# GWLSensorv5.net
KiCad netlist of a schematic drawn in EAGLE
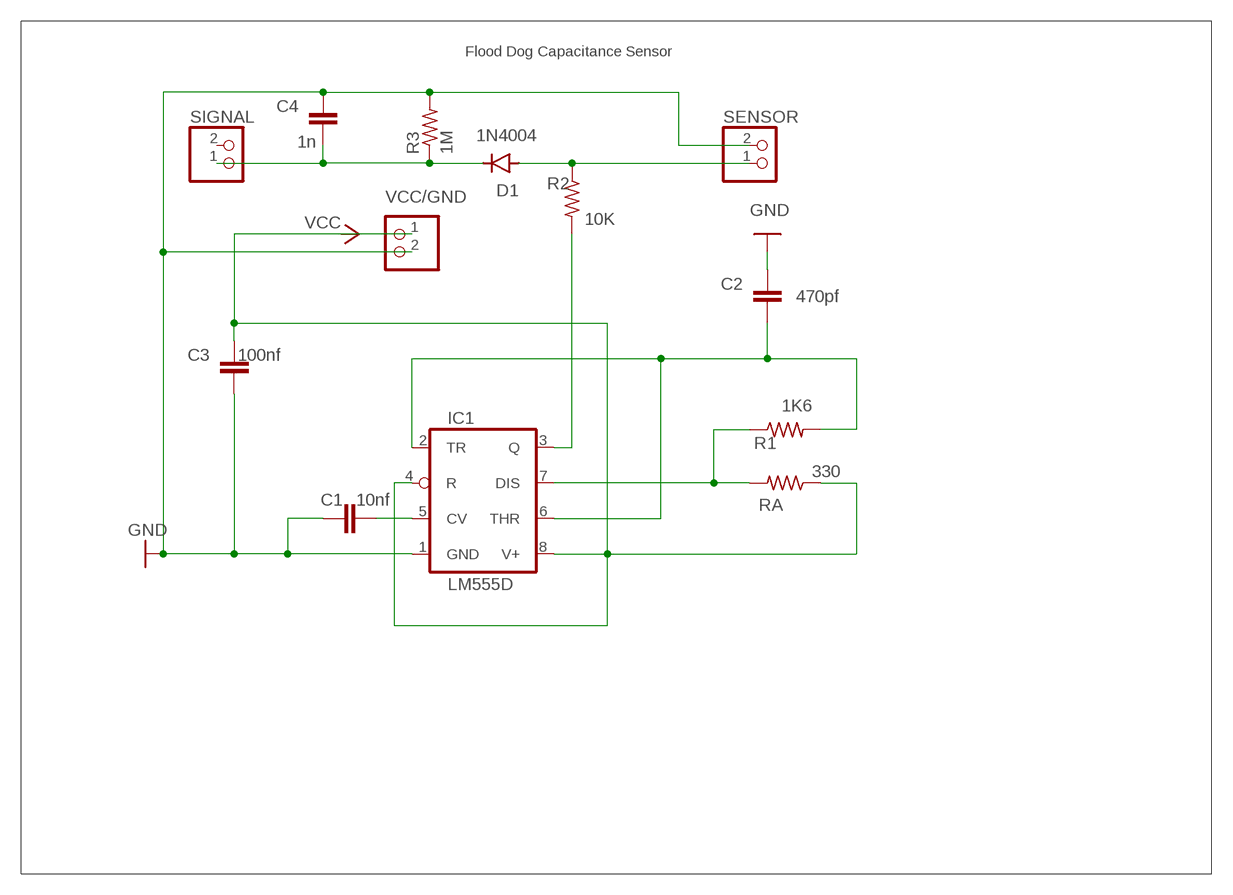
[diagram p0: schematic, sheet 1]

(export (version "E")
  (design (tool "Eeschema 10.0.6"))
  (components
    (comp (ref "C1")
      (value "10nf")
      (footprint "eagle-import:C0805")
      (libsource (lib "eagle-import") (part "C-EUC0805"))
    )
    (comp (ref "C2")
      (value "470pf")
      (footprint "eagle-import:C0805")
      (libsource (lib "eagle-import") (part "C-EUC0805"))
    )
    (comp (ref "C3")
      (value "100nf")
      (footprint "eagle-import:C0805")
      (libsource (lib "eagle-import") (part "C-EUC0805"))
    )
    (comp (ref "C4")
      (value "1n")
      (footprint "eagle-import:C0805")
      (libsource (lib "eagle-import") (part "C-EUC0805"))
    )
    (comp (ref "D1")
      (value "1N4004")
      (footprint "eagle-import:DO41-10")
      (libsource (lib "eagle-import") (part "1N4004"))
    )
    (comp (ref "IC1")
      (value "LM555D")
      (footprint "eagle-import:SO08")
      (libsource (lib "eagle-import") (part "555DLM"))
    )
    (comp (ref "R1")
      (value "1K6")
      (footprint "eagle-import:R0805")
      (libsource (lib "eagle-import") (part "R-US_R0805"))
    )
    (comp (ref "R2")
      (value "10K")
      (footprint "eagle-import:R0805")
      (libsource (lib "eagle-import") (part "R-US_R0805"))
    )
    (comp (ref "R3")
      (value "1M")
      (footprint "eagle-import:R0805")
      (libsource (lib "eagle-import") (part "R-US_R0805"))
    )
    (comp (ref "RA")
      (value "330")
      (footprint "eagle-import:R0805")
      (libsource (lib "eagle-import") (part "R-US_R0805"))
    )
    (comp (ref "SENSOR")
      (value "JST_2PIN-SMT")
      (footprint "eagle-import:JST-PH-2-SMT")
      (libsource (lib "eagle-import") (part "JST_2PIN-SMT"))
    )
    (comp (ref "SIGNAL")
      (value "JST_2PIN-SMT")
      (footprint "eagle-import:JST-PH-2-SMT")
      (libsource (lib "eagle-import") (part "JST_2PIN-SMT"))
    )
    (comp (ref "VCC/GND")
      (value "JST_2PIN-SMT")
      (footprint "eagle-import:JST-PH-2-SMT")
      (libsource (lib "eagle-import") (part "JST_2PIN-SMT"))
    )
  )
  (nets
    (net (code "1") (name "GND") (class "Default")
      (node (ref "C1") (pin "1") (pinfunction "1_1") (pintype "passive"))
      (node (ref "C2") (pin "2") (pinfunction "2_2") (pintype "passive"))
      (node (ref "C3") (pin "1") (pinfunction "1_1") (pintype "passive"))
      (node (ref "C4") (pin "2") (pinfunction "2_2") (pintype "passive"))
      (node (ref "IC1") (pin "1") (pinfunction "GND_1") (pintype "power_in"))
      (node (ref "R3") (pin "2") (pinfunction "2_2") (pintype "passive"))
      (node (ref "SENSOR") (pin "2") (pinfunction "1_2") (pintype "passive"))
      (node (ref "VCC/GND") (pin "2") (pinfunction "1_2") (pintype "passive"))
    )
    (net (code "2") (name "Net-(IC1-CV)") (class "Default")
      (node (ref "C1") (pin "2") (pinfunction "2_2") (pintype "passive"))
      (node (ref "IC1") (pin "5") (pinfunction "CV_5") (pintype "input"))
    )
    (net (code "3") (name "Net-(IC1-DIS)") (class "Default")
      (node (ref "IC1") (pin "7") (pinfunction "DIS_7") (pintype "input"))
      (node (ref "R1") (pin "1") (pinfunction "1_1") (pintype "passive"))
      (node (ref "RA") (pin "2") (pinfunction "2_2") (pintype "passive"))
    )
    (net (code "4") (name "Net-(IC1-Q)") (class "Default")
      (node (ref "IC1") (pin "3") (pinfunction "Q_3") (pintype "output"))
      (node (ref "R2") (pin "2") (pinfunction "2_2") (pintype "passive"))
    )
    (net (code "5") (name "Net-(IC1-THR)") (class "Default")
      (node (ref "C2") (pin "1") (pinfunction "1_1") (pintype "passive"))
      (node (ref "IC1") (pin "2") (pinfunction "TR_2") (pintype "input"))
      (node (ref "IC1") (pin "6") (pinfunction "THR_6") (pintype "input"))
      (node (ref "R1") (pin "2") (pinfunction "2_2") (pintype "passive"))
    )
    (net (code "6") (name "Net-(SENSOR-2)") (class "Default")
      (node (ref "D1") (pin "A") (pinfunction "A_A") (pintype "passive"))
      (node (ref "R2") (pin "1") (pinfunction "1_1") (pintype "passive"))
      (node (ref "SENSOR") (pin "1") (pinfunction "2_1") (pintype "passive"))
    )
    (net (code "7") (name "Net-(SIGNAL-2)") (class "Default")
      (node (ref "C4") (pin "1") (pinfunction "1_1") (pintype "passive"))
      (node (ref "D1") (pin "C") (pinfunction "C_C") (pintype "passive"))
      (node (ref "R3") (pin "1") (pinfunction "1_1") (pintype "passive"))
      (node (ref "SIGNAL") (pin "1") (pinfunction "2_1") (pintype "passive"))
    )
    (net (code "8") (name "VCC") (class "Default")
      (node (ref "C3") (pin "2") (pinfunction "2_2") (pintype "passive"))
      (node (ref "IC1") (pin "4") (pinfunction "R_4") (pintype "input"))
      (node (ref "IC1") (pin "8") (pinfunction "V+_8") (pintype "power_in"))
      (node (ref "RA") (pin "1") (pinfunction "1_1") (pintype "passive"))
      (node (ref "VCC/GND") (pin "1") (pinfunction "2_1") (pintype "passive"))
    )
    (net (code "9") (name "unconnected-(SIGNAL-1-Pad2)") (class "Default")
      (node (ref "SIGNAL") (pin "2") (pinfunction "1_2") (pintype "passive"))
    )
  )
)
